# batteryless_design_revA.net
KiCad netlist of a schematic drawn in EAGLE
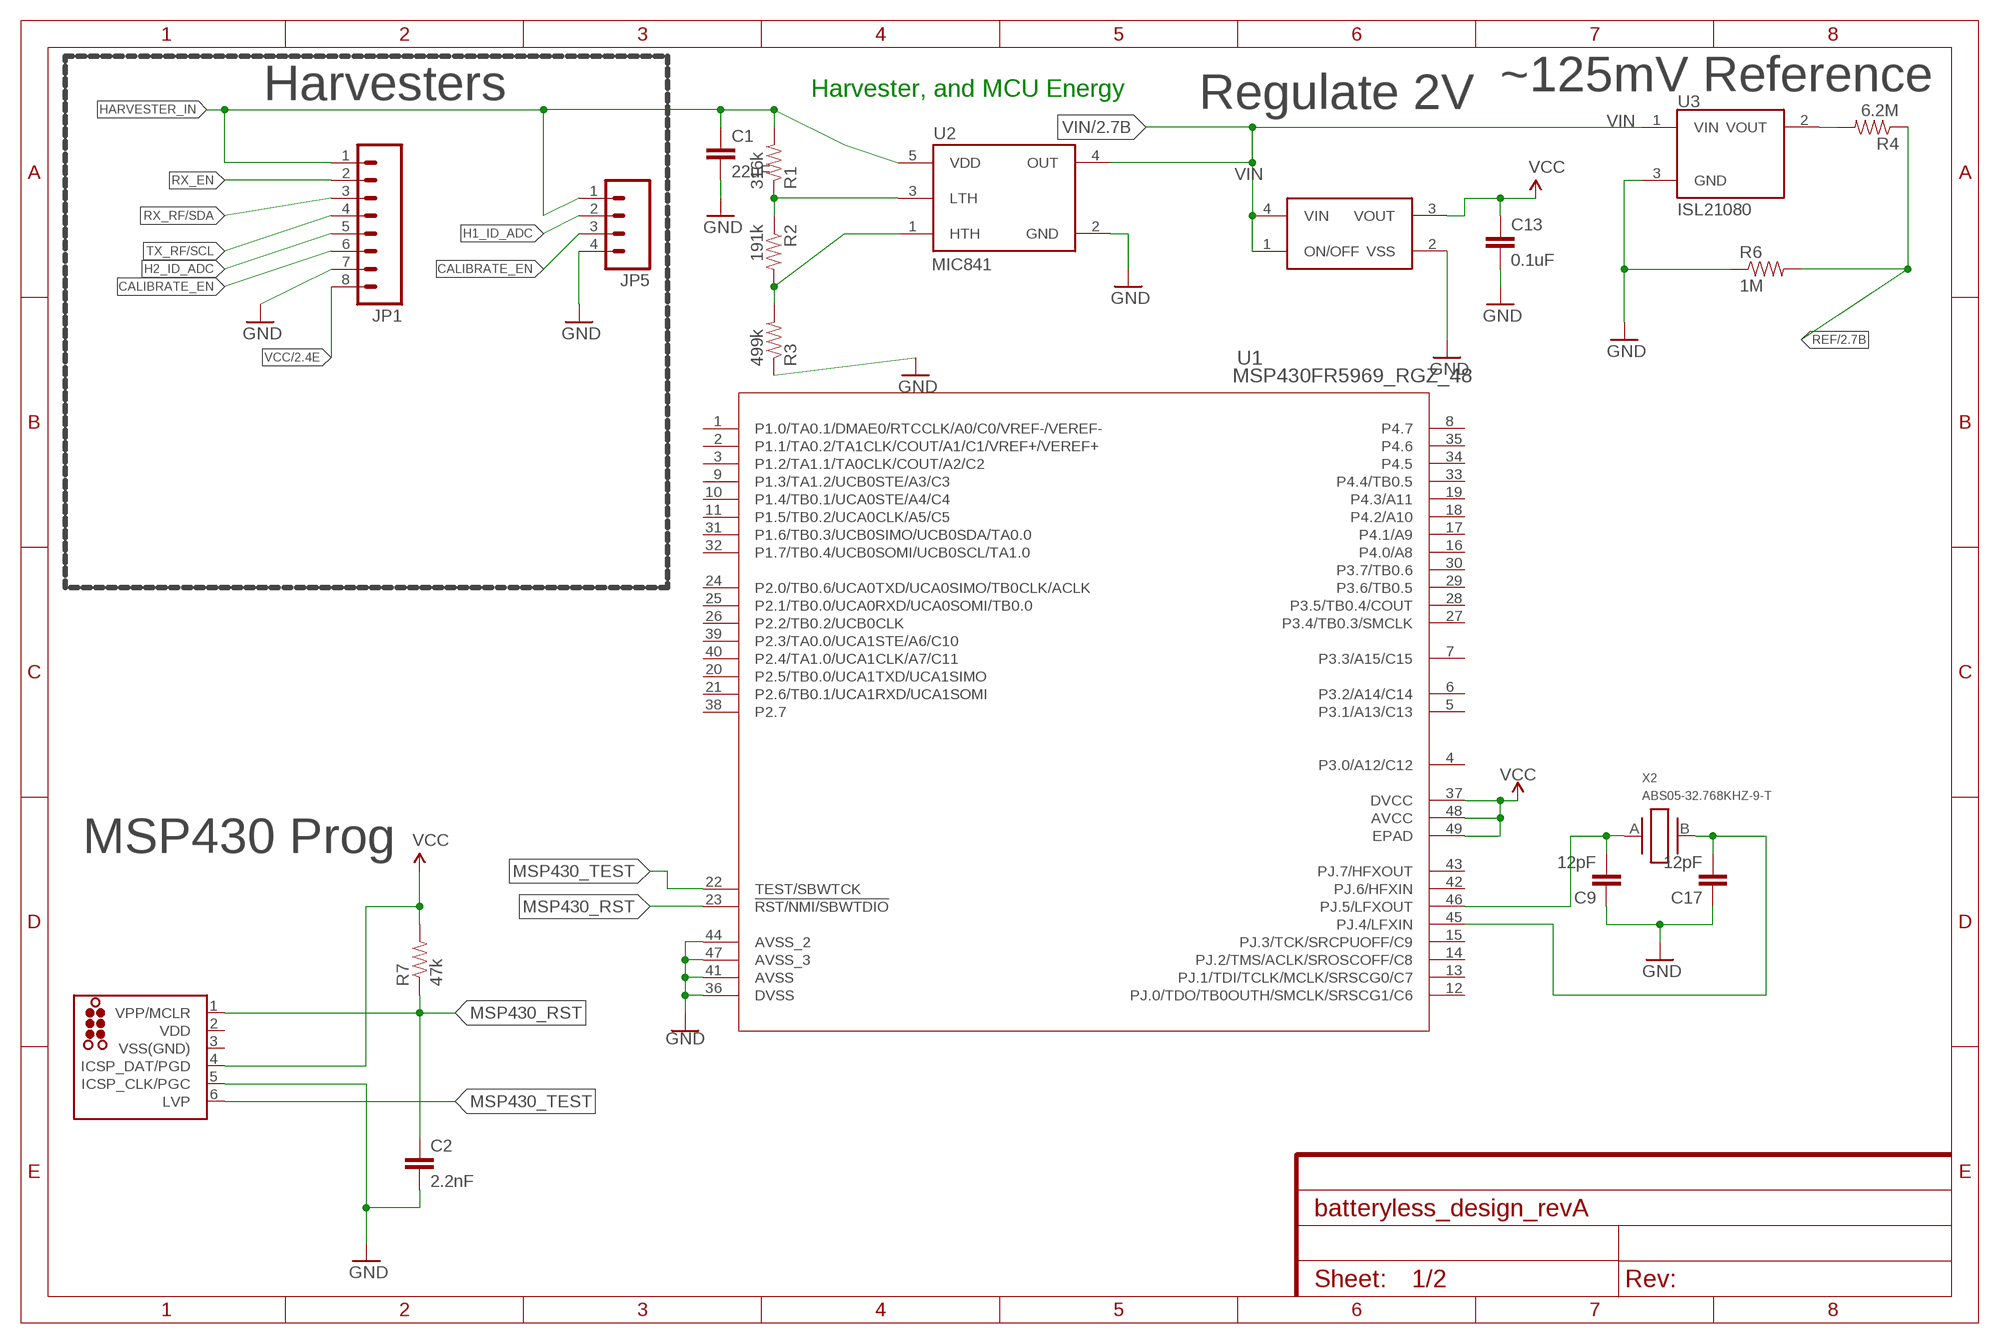
[diagram p0: schematic, sheet 1]
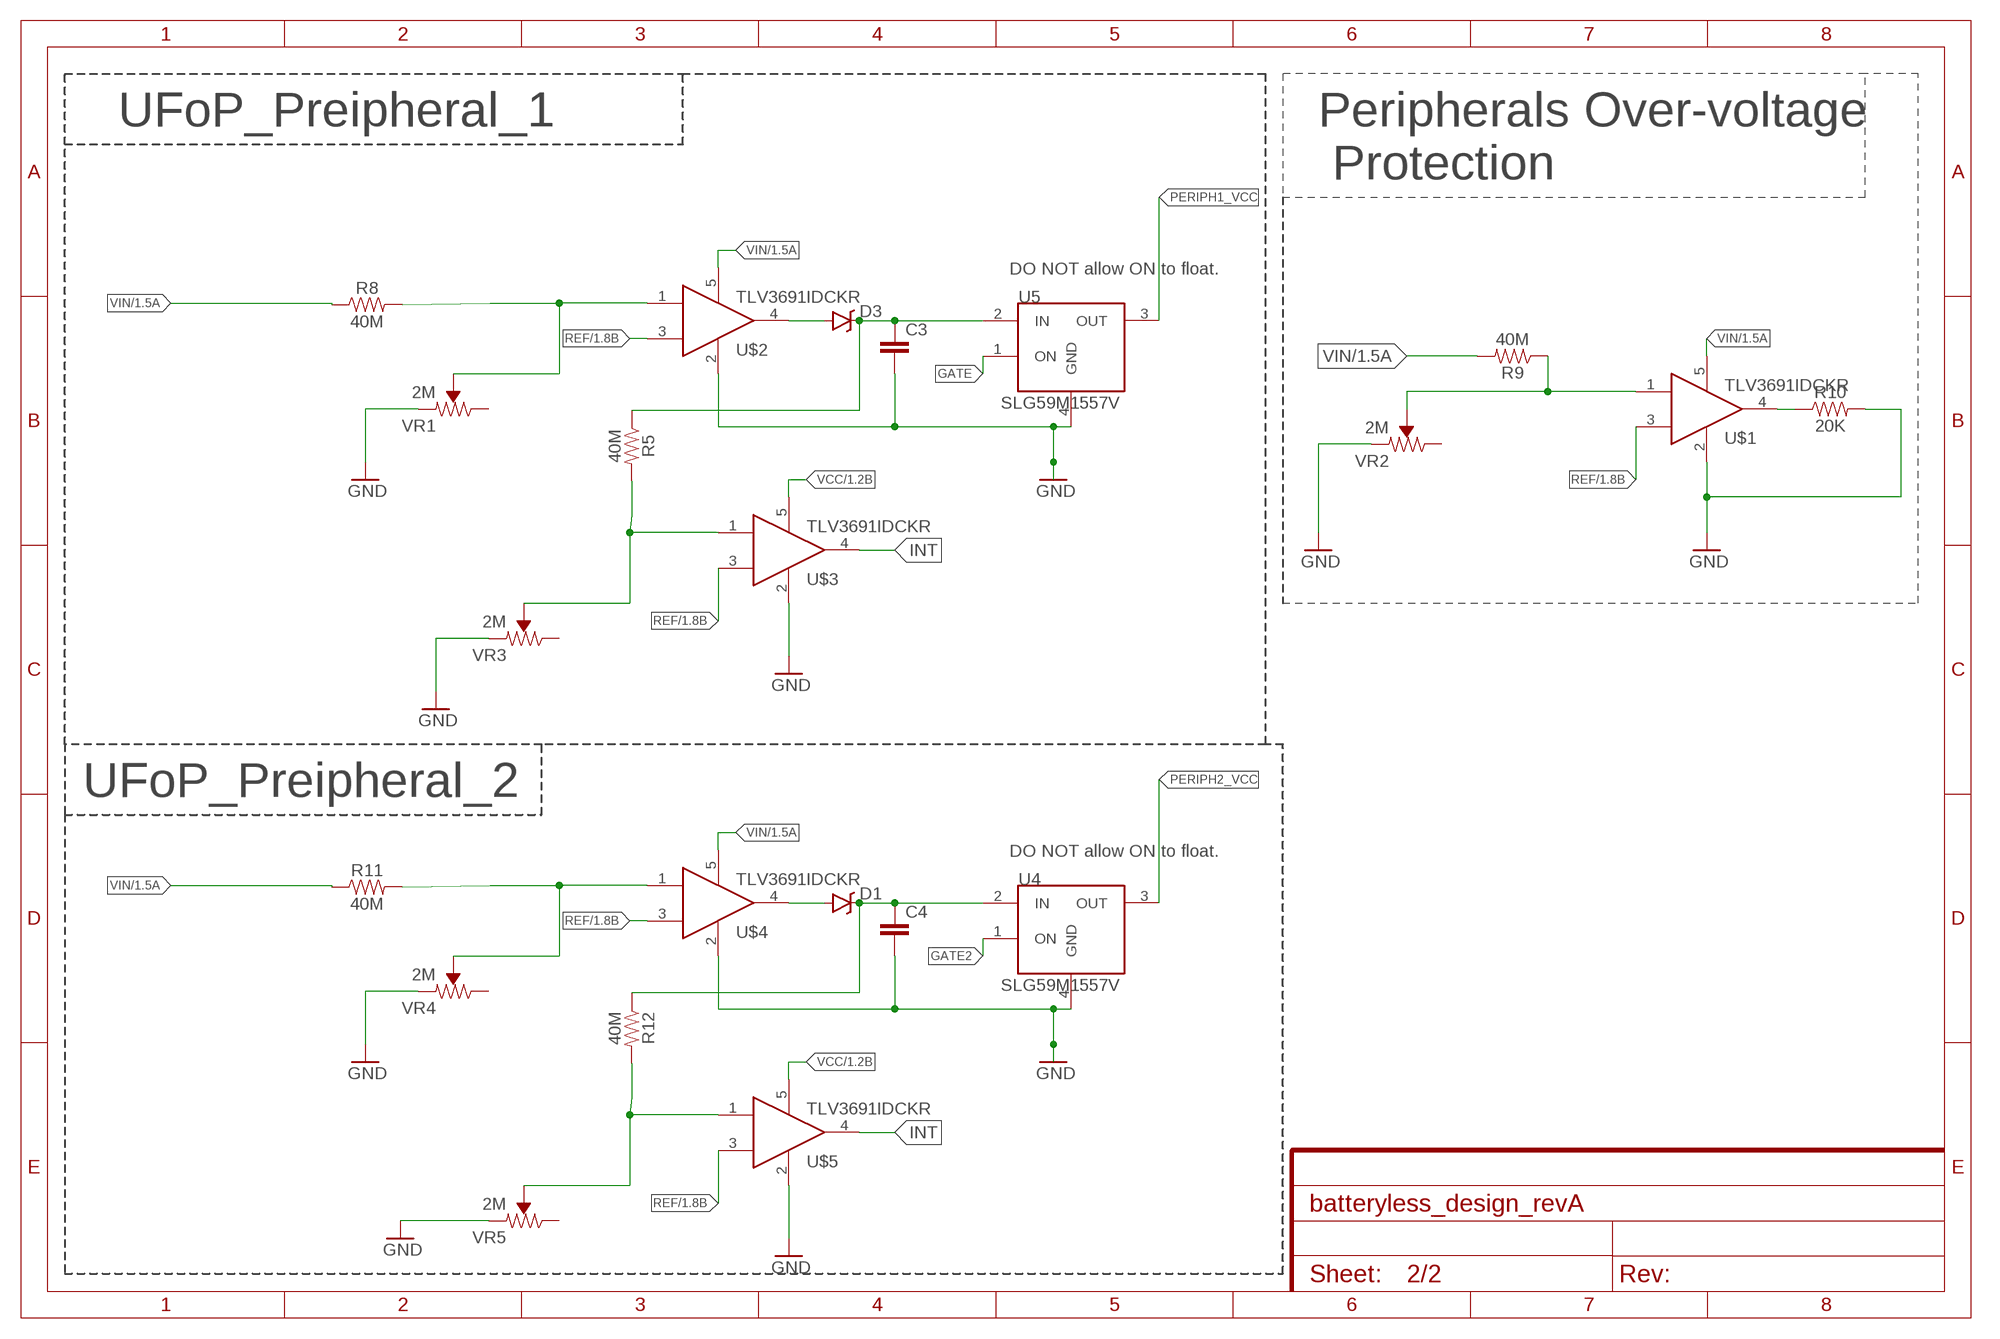
[diagram p1: schematic, sheet 2]

(export (version "E")
  (design (tool "Eeschema 10.0.6"))
  (components
    (comp (ref "C1")
      (value "22uF")
      (footprint "eagle-import:1210")
      (fields (field (name "MANUFACTURERPARTNUMBER") "  CL32A226KAJNNNE"))
      (libsource (lib "eagle-import") (part "CAP1210"))
    )
    (comp (ref "C2")
      (value "2.2nF")
      (footprint "eagle-import:0603")
      (fields (field (name "MPN") "  06035C222KAT2A"))
      (libsource (lib "eagle-import") (part "C-EU0603"))
    )
    (comp (ref "C9")
      (value "12pF")
      (footprint "eagle-import:0603")
      (fields (field (name "MPN") "CL10C120JB8NNNC"))
      (libsource (lib "eagle-import") (part "C-EU0603"))
    )
    (comp (ref "C13")
      (value "0.1uF")
      (footprint "eagle-import:0603")
      (fields (field (name "MANUFACTURERPARTNUMBER") "  0603YC104KAT2A"))
      (libsource (lib "eagle-import") (part "C-EU0603"))
    )
    (comp (ref "C17")
      (value "12pF")
      (footprint "eagle-import:0603")
      (fields (field (name "MPN") "CL10C120JB8NNNC"))
      (libsource (lib "eagle-import") (part "C-EU0603"))
    )
    (comp (ref "J1")
      (value "TC2030-MCP-NL")
      (footprint "eagle-import:TC2030-MCP-NL")
      (libsource (lib "eagle-import") (part "TC2030-MCP-NL"))
    )
    (comp (ref "JP1")
      (value "M081.27MM")
      (footprint "eagle-import:1X08-1.27MM")
      (fields (field (name "MANUFACTURERPARTNUMBER") "851-43-008-10-001000 "))
      (libsource (lib "eagle-import") (part "M081.27MM"))
    )
    (comp (ref "JP5")
      (value "M041.27MM")
      (footprint "eagle-import:1X04-1.27MM")
      (fields (field (name "MANUFACTURERPARTNUMBER") "851-43-004-10-001000 "))
      (libsource (lib "eagle-import") (part "M041.27MM"))
    )
    (comp (ref "R1")
      (value "316k")
      (footprint "eagle-import:0603")
      (fields (field (name "MANUFACTURERPARTNUMBER") "RC0603FR-07316KL "))
      (libsource (lib "eagle-import") (part "R-EU0603"))
    )
    (comp (ref "R2")
      (value "191k")
      (footprint "eagle-import:0603")
      (fields (field (name "MANUFACTURERPARTNUMBER") "RC0603FR-07191KL "))
      (libsource (lib "eagle-import") (part "R-EU0603"))
    )
    (comp (ref "R3")
      (value "499k")
      (footprint "eagle-import:0603")
      (fields (field (name "MANUFACTURERPARTNUMBER") "RC0603FR-07499KL"))
      (libsource (lib "eagle-import") (part "R-EU0603"))
    )
    (comp (ref "R4")
      (value "6.2M")
      (footprint "eagle-import:0603")
      (fields (field (name "MPN") "CRCW06036M20FKEA"))
      (libsource (lib "eagle-import") (part "R-EU0603"))
    )
    (comp (ref "R6")
      (value "1M")
      (footprint "eagle-import:0603")
      (fields (field (name "MPN") "RC0603FR-071ML"))
      (libsource (lib "eagle-import") (part "R-EU0603"))
    )
    (comp (ref "R7")
      (value "47k")
      (footprint "eagle-import:0603")
      (fields (field (name "MPN") "  CRCW060347K0JNEA"))
      (libsource (lib "eagle-import") (part "R-EU0603"))
    )
    (comp (ref "U$6")
      (value "S-1313")
      (footprint "eagle-import:SC82-AB_1PRIMARY")
      (libsource (lib "eagle-import") (part "S-1313"))
    )
    (comp (ref "U1")
      (value "MSP430FR5969_RGZ_48")
      (footprint "eagle-import:RGZ48_4P1X4P1")
      (fields (field (name "MANUFACTURER_PART_NUMBER") "msp430fr5969_rgz_48"))
      (libsource (lib "eagle-import") (part "MSP430FR5969_RGZ_48"))
    )
    (comp (ref "U2")
      (value "MIC841")
      (footprint "eagle-import:SC70-5")
      (fields (field (name "MPN") "MIC841HYC5-TR"))
      (libsource (lib "eagle-import") (part "MIC841"))
    )
    (comp (ref "U3")
      (value "ISL21080")
      (footprint "eagle-import:SOT-23")
      (fields (field (name "MPN") "ISL21080DIH309Z-TK"))
      (libsource (lib "eagle-import") (part "ISL21080"))
    )
    (comp (ref "X2")
      (value "ABS05-32.768KHZ-9-T")
      (footprint "eagle-import:ABS05")
      (fields (field (name "MPN") "ABS05-32.768KHZ-9-T "))
      (libsource (lib "eagle-import") (part "ABS05-32.768KHZ-9-T"))
    )
    (comp (ref "C3")
      (value "0.1UF-0603-25V-(+80/-20%)")
      (footprint "eagle-import:0603")
      (libsource (lib "eagle-import") (part "0.1UF-0603-25V-(+80/-20%)"))
    )
    (comp (ref "C4")
      (value "0.1UF-0603-25V-(+80/-20%)")
      (footprint "eagle-import:0603")
      (libsource (lib "eagle-import") (part "0.1UF-0603-25V-(+80/-20%)"))
    )
    (comp (ref "D1")
      (value "RB751")
      (footprint "eagle-import:SOD-523")
      (fields (field (name "MPN") "BAS40-02V-V-G-08"))
      (libsource (lib "eagle-import") (part "DIODE-SCHOTTKY-RB751"))
    )
    (comp (ref "D3")
      (value "RB751")
      (footprint "eagle-import:SOD-523")
      (fields (field (name "MPN") "BAS40-02V-V-G-08"))
      (libsource (lib "eagle-import") (part "DIODE-SCHOTTKY-RB751"))
    )
    (comp (ref "R5")
      (value "40M")
      (footprint "eagle-import:0805")
      (libsource (lib "eagle-import") (part "0.3OHM-0805-1/8W-1%"))
    )
    (comp (ref "R8")
      (value "40M")
      (footprint "eagle-import:0805")
      (libsource (lib "eagle-import") (part "0.3OHM-0805-1/8W-1%"))
    )
    (comp (ref "R9")
      (value "40M")
      (footprint "eagle-import:0805")
      (libsource (lib "eagle-import") (part "0.3OHM-0805-1/8W-1%"))
    )
    (comp (ref "R10")
      (value "20K")
      (footprint "eagle-import:0805")
      (libsource (lib "eagle-import") (part "0.3OHM-0805-1/8W-1%"))
    )
    (comp (ref "R11")
      (value "40M")
      (footprint "eagle-import:0805")
      (libsource (lib "eagle-import") (part "0.3OHM-0805-1/8W-1%"))
    )
    (comp (ref "R12")
      (value "40M")
      (footprint "eagle-import:0805")
      (libsource (lib "eagle-import") (part "0.3OHM-0805-1/8W-1%"))
    )
    (comp (ref "U$1")
      (value "TLV3691IDCKR")
      (footprint "eagle-import:SOT353")
      (libsource (lib "eagle-import") (part "TLV3691IDCKR"))
    )
    (comp (ref "U$2")
      (value "TLV3691IDCKR")
      (footprint "eagle-import:SOT353")
      (libsource (lib "eagle-import") (part "TLV3691IDCKR"))
    )
    (comp (ref "U$3")
      (value "TLV3691IDCKR")
      (footprint "eagle-import:SOT353")
      (libsource (lib "eagle-import") (part "TLV3691IDCKR"))
    )
    (comp (ref "U$4")
      (value "TLV3691IDCKR")
      (footprint "eagle-import:SOT353")
      (libsource (lib "eagle-import") (part "TLV3691IDCKR"))
    )
    (comp (ref "U$5")
      (value "TLV3691IDCKR")
      (footprint "eagle-import:SOT353")
      (libsource (lib "eagle-import") (part "TLV3691IDCKR"))
    )
    (comp (ref "U4")
      (value "SLG59M1557V")
      (footprint "eagle-import:4STDFN")
      (fields (field (name "MPN") "SLG59M1557V "))
      (libsource (lib "eagle-import") (part "SLG59M1557V"))
    )
    (comp (ref "U5")
      (value "SLG59M1557V")
      (footprint "eagle-import:4STDFN")
      (fields (field (name "MPN") "SLG59M1557V "))
      (libsource (lib "eagle-import") (part "SLG59M1557V"))
    )
    (comp (ref "VR1")
      (value "2M")
      (footprint "eagle-import:TRIMPOT-SMD-3MM-CLOSED")
      (libsource (lib "eagle-import") (part "TRIMPOT-SMD-3MM-CLOSED-1/8W-20%"))
    )
    (comp (ref "VR2")
      (value "2M")
      (footprint "eagle-import:TRIMPOT-SMD-3MM-CLOSED")
      (libsource (lib "eagle-import") (part "TRIMPOT-SMD-3MM-CLOSED-1/8W-20%"))
    )
    (comp (ref "VR3")
      (value "2M")
      (footprint "eagle-import:TRIMPOT-SMD-3MM-CLOSED")
      (libsource (lib "eagle-import") (part "TRIMPOT-SMD-3MM-CLOSED-1/8W-20%"))
    )
    (comp (ref "VR4")
      (value "2M")
      (footprint "eagle-import:TRIMPOT-SMD-3MM-CLOSED")
      (libsource (lib "eagle-import") (part "TRIMPOT-SMD-3MM-CLOSED-1/8W-20%"))
    )
    (comp (ref "VR5")
      (value "2M")
      (footprint "eagle-import:TRIMPOT-SMD-3MM-CLOSED")
      (libsource (lib "eagle-import") (part "TRIMPOT-SMD-3MM-CLOSED-1/8W-20%"))
    )
  )
  (nets
    (net (code "1") (name "CALIBRATE_EN") (class "Default")
      (node (ref "JP1") (pin "6") (pinfunction "6_6") (pintype "passive"))
      (node (ref "JP5") (pin "3") (pinfunction "3_3") (pintype "passive"))
    )
    (net (code "2") (name "GATE") (class "Default")
      (node (ref "U5") (pin "1") (pinfunction "ON_1") (pintype "bidirectional"))
    )
    (net (code "3") (name "GATE2") (class "Default")
      (node (ref "U4") (pin "1") (pinfunction "ON_1") (pintype "bidirectional"))
    )
    (net (code "4") (name "GND") (class "Default")
      (node (ref "C1") (pin "2") (pinfunction "2_2") (pintype "passive"))
      (node (ref "C13") (pin "2") (pinfunction "2_2") (pintype "passive"))
      (node (ref "C17") (pin "1") (pinfunction "1_1") (pintype "passive"))
      (node (ref "C2") (pin "2") (pinfunction "2_2") (pintype "passive"))
      (node (ref "C3") (pin "2") (pinfunction "2_2") (pintype "passive"))
      (node (ref "C4") (pin "2") (pinfunction "2_2") (pintype "passive"))
      (node (ref "C9") (pin "1") (pinfunction "1_1") (pintype "passive"))
      (node (ref "J1") (pin "5") (pinfunction "ICSP_CLK/PGC_5") (pintype "output"))
      (node (ref "JP1") (pin "7") (pinfunction "7_7") (pintype "passive"))
      (node (ref "JP5") (pin "4") (pinfunction "4_4") (pintype "passive"))
      (node (ref "R10") (pin "2") (pinfunction "2_2") (pintype "passive"))
      (node (ref "R3") (pin "1") (pinfunction "1_1") (pintype "passive"))
      (node (ref "R6") (pin "1") (pinfunction "1_1") (pintype "passive"))
      (node (ref "U$1") (pin "2") (pinfunction "2_2") (pintype "bidirectional"))
      (node (ref "U$2") (pin "2") (pinfunction "2_2") (pintype "bidirectional"))
      (node (ref "U$3") (pin "2") (pinfunction "2_2") (pintype "bidirectional"))
      (node (ref "U$4") (pin "2") (pinfunction "2_2") (pintype "bidirectional"))
      (node (ref "U$5") (pin "2") (pinfunction "2_2") (pintype "bidirectional"))
      (node (ref "U$6") (pin "2") (pinfunction "VSS_2") (pintype "bidirectional"))
      (node (ref "U1") (pin "36") (pinfunction "DVSS_36") (pintype "power_in"))
      (node (ref "U1") (pin "41") (pinfunction "AVSS_41") (pintype "power_in"))
      (node (ref "U1") (pin "44") (pinfunction "AVSS_2_44") (pintype "power_in"))
      (node (ref "U1") (pin "47") (pinfunction "AVSS_3_47") (pintype "power_in"))
      (node (ref "U2") (pin "2") (pinfunction "GND_2") (pintype "bidirectional"))
      (node (ref "U3") (pin "3") (pinfunction "GND_3") (pintype "bidirectional"))
      (node (ref "U4") (pin "4") (pinfunction "GND_4") (pintype "bidirectional"))
      (node (ref "U5") (pin "4") (pinfunction "GND_4") (pintype "bidirectional"))
      (node (ref "VR1") (pin "1") (pinfunction "CCW_1") (pintype "passive"))
      (node (ref "VR2") (pin "1") (pinfunction "CCW_1") (pintype "passive"))
      (node (ref "VR3") (pin "1") (pinfunction "CCW_1") (pintype "passive"))
      (node (ref "VR4") (pin "1") (pinfunction "CCW_1") (pintype "passive"))
      (node (ref "VR5") (pin "1") (pinfunction "CCW_1") (pintype "passive"))
    )
    (net (code "5") (name "H1_ID_ADC") (class "Default")
      (node (ref "JP5") (pin "2") (pinfunction "2_2") (pintype "passive"))
    )
    (net (code "6") (name "H2_ID_ADC") (class "Default")
      (node (ref "JP1") (pin "5") (pinfunction "5_5") (pintype "passive"))
    )
    (net (code "7") (name "HARVESTER_IN") (class "Default")
      (node (ref "C1") (pin "1") (pinfunction "1_1") (pintype "passive"))
      (node (ref "JP1") (pin "1") (pinfunction "1_1") (pintype "passive"))
      (node (ref "JP5") (pin "1") (pinfunction "1_1") (pintype "passive"))
      (node (ref "R1") (pin "2") (pinfunction "2_2") (pintype "passive"))
      (node (ref "U2") (pin "5") (pinfunction "VDD_5") (pintype "bidirectional"))
    )
    (net (code "8") (name "INT") (class "Default")
      (node (ref "U$3") (pin "4") (pinfunction "4_4") (pintype "bidirectional"))
      (node (ref "U$5") (pin "4") (pinfunction "4_4") (pintype "bidirectional"))
    )
    (net (code "9") (name "MSP430_RST") (class "Default")
      (node (ref "C2") (pin "1") (pinfunction "1_1") (pintype "passive"))
      (node (ref "J1") (pin "1") (pinfunction "VPP/MCLR_1") (pintype "passive"))
      (node (ref "R7") (pin "1") (pinfunction "1_1") (pintype "passive"))
    )
    (net (code "10") (name "MSP430_TEST") (class "Default")
      (node (ref "J1") (pin "6") (pinfunction "LVP_6") (pintype "bidirectional"))
    )
    (net (code "11") (name "Net-(D1-PadA)") (class "Default")
      (node (ref "D1") (pin "A") (pinfunction "A_A") (pintype "passive"))
      (node (ref "U$4") (pin "4") (pinfunction "4_4") (pintype "bidirectional"))
    )
    (net (code "12") (name "Net-(D3-PadA)") (class "Default")
      (node (ref "D3") (pin "A") (pinfunction "A_A") (pintype "passive"))
      (node (ref "U$2") (pin "4") (pinfunction "4_4") (pintype "bidirectional"))
    )
    (net (code "13") (name "Net-(R10-Pad1)") (class "Default")
      (node (ref "R10") (pin "1") (pinfunction "1_1") (pintype "passive"))
      (node (ref "U$1") (pin "4") (pinfunction "4_4") (pintype "bidirectional"))
    )
    (net (code "14") (name "Net-(U1-PJ.4{slash}LFXIN)") (class "Default")
      (node (ref "C17") (pin "2") (pinfunction "2_2") (pintype "passive"))
      (node (ref "U1") (pin "45") (pinfunction "PJ.4/LFXIN_45") (pintype "passive"))
      (node (ref "X2") (pin "B") (pinfunction "2_B") (pintype "bidirectional"))
    )
    (net (code "15") (name "Net-(U1-PJ.5{slash}LFXOUT)") (class "Default")
      (node (ref "C9") (pin "2") (pinfunction "2_2") (pintype "passive"))
      (node (ref "U1") (pin "46") (pinfunction "PJ.5/LFXOUT_46") (pintype "passive"))
      (node (ref "X2") (pin "A") (pinfunction "1_A") (pintype "bidirectional"))
    )
    (net (code "16") (name "Net-(U2-HTH)") (class "Default")
      (node (ref "R2") (pin "2") (pinfunction "2_2") (pintype "passive"))
      (node (ref "R3") (pin "2") (pinfunction "2_2") (pintype "passive"))
      (node (ref "U2") (pin "1") (pinfunction "HTH_1") (pintype "bidirectional"))
    )
    (net (code "17") (name "Net-(U2-LTH)") (class "Default")
      (node (ref "R1") (pin "1") (pinfunction "1_1") (pintype "passive"))
      (node (ref "R2") (pin "1") (pinfunction "1_1") (pintype "passive"))
      (node (ref "U2") (pin "3") (pinfunction "LTH_3") (pintype "bidirectional"))
    )
    (net (code "18") (name "Net-(U3-VOUT)") (class "Default")
      (node (ref "R4") (pin "2") (pinfunction "2_2") (pintype "passive"))
      (node (ref "U3") (pin "2") (pinfunction "VOUT_2") (pintype "bidirectional"))
    )
    (net (code "19") (name "Net-(U4-IN)") (class "Default")
      (node (ref "C4") (pin "1") (pinfunction "1_1") (pintype "passive"))
      (node (ref "D1") (pin "C") (pinfunction "C_C") (pintype "passive"))
      (node (ref "R12") (pin "1") (pinfunction "1_1") (pintype "passive"))
      (node (ref "U4") (pin "2") (pinfunction "IN_2") (pintype "bidirectional"))
    )
    (net (code "20") (name "Net-(U5-IN)") (class "Default")
      (node (ref "C3") (pin "1") (pinfunction "1_1") (pintype "passive"))
      (node (ref "D3") (pin "C") (pinfunction "C_C") (pintype "passive"))
      (node (ref "R5") (pin "1") (pinfunction "1_1") (pintype "passive"))
      (node (ref "U5") (pin "2") (pinfunction "IN_2") (pintype "bidirectional"))
    )
    (net (code "21") (name "Net-(VR1-WIPER)") (class "Default")
      (node (ref "R8") (pin "2") (pinfunction "2_2") (pintype "passive"))
      (node (ref "U$2") (pin "1") (pinfunction "1_1") (pintype "bidirectional"))
      (node (ref "VR1") (pin "2") (pinfunction "WIPER_2") (pintype "passive"))
    )
    (net (code "22") (name "Net-(VR2-WIPER)") (class "Default")
      (node (ref "R9") (pin "1") (pinfunction "1_1") (pintype "passive"))
      (node (ref "U$1") (pin "1") (pinfunction "1_1") (pintype "bidirectional"))
      (node (ref "VR2") (pin "2") (pinfunction "WIPER_2") (pintype "passive"))
    )
    (net (code "23") (name "Net-(VR3-WIPER)") (class "Default")
      (node (ref "R5") (pin "2") (pinfunction "2_2") (pintype "passive"))
      (node (ref "U$3") (pin "1") (pinfunction "1_1") (pintype "bidirectional"))
      (node (ref "VR3") (pin "2") (pinfunction "WIPER_2") (pintype "passive"))
    )
    (net (code "24") (name "Net-(VR4-WIPER)") (class "Default")
      (node (ref "R11") (pin "2") (pinfunction "2_2") (pintype "passive"))
      (node (ref "U$4") (pin "1") (pinfunction "1_1") (pintype "bidirectional"))
      (node (ref "VR4") (pin "2") (pinfunction "WIPER_2") (pintype "passive"))
    )
    (net (code "25") (name "Net-(VR5-WIPER)") (class "Default")
      (node (ref "R12") (pin "2") (pinfunction "2_2") (pintype "passive"))
      (node (ref "U$5") (pin "1") (pinfunction "1_1") (pintype "bidirectional"))
      (node (ref "VR5") (pin "2") (pinfunction "WIPER_2") (pintype "passive"))
    )
    (net (code "26") (name "PERIPH1_VCC") (class "Default")
      (node (ref "U5") (pin "3") (pinfunction "OUT_3") (pintype "bidirectional"))
    )
    (net (code "27") (name "PERIPH2_VCC") (class "Default")
      (node (ref "U4") (pin "3") (pinfunction "OUT_3") (pintype "bidirectional"))
    )
    (net (code "28") (name "REF") (class "Default")
      (node (ref "R4") (pin "1") (pinfunction "1_1") (pintype "passive"))
      (node (ref "R6") (pin "2") (pinfunction "2_2") (pintype "passive"))
      (node (ref "U$1") (pin "3") (pinfunction "3_3") (pintype "bidirectional"))
      (node (ref "U$2") (pin "3") (pinfunction "3_3") (pintype "bidirectional"))
      (node (ref "U$3") (pin "3") (pinfunction "3_3") (pintype "bidirectional"))
      (node (ref "U$4") (pin "3") (pinfunction "3_3") (pintype "bidirectional"))
      (node (ref "U$5") (pin "3") (pinfunction "3_3") (pintype "bidirectional"))
    )
    (net (code "29") (name "RX_EN") (class "Default")
      (node (ref "JP1") (pin "2") (pinfunction "2_2") (pintype "passive"))
    )
    (net (code "30") (name "RX_RF{slash}SDA") (class "Default")
      (node (ref "JP1") (pin "3") (pinfunction "3_3") (pintype "passive"))
    )
    (net (code "31") (name "TX_RF{slash}SCL") (class "Default")
      (node (ref "JP1") (pin "4") (pinfunction "4_4") (pintype "passive"))
    )
    (net (code "32") (name "VCC") (class "Default")
      (node (ref "C13") (pin "1") (pinfunction "1_1") (pintype "passive"))
      (node (ref "J1") (pin "4") (pinfunction "ICSP_DAT/PGD_4") (pintype "bidirectional"))
      (node (ref "JP1") (pin "8") (pinfunction "8_8") (pintype "passive"))
      (node (ref "R7") (pin "2") (pinfunction "2_2") (pintype "passive"))
      (node (ref "U$3") (pin "5") (pinfunction "5_5") (pintype "bidirectional"))
      (node (ref "U$5") (pin "5") (pinfunction "5_5") (pintype "bidirectional"))
      (node (ref "U$6") (pin "3") (pinfunction "VOUT_3") (pintype "bidirectional"))
      (node (ref "U1") (pin "37") (pinfunction "DVCC_37") (pintype "power_in"))
      (node (ref "U1") (pin "48") (pinfunction "AVCC_48") (pintype "power_in"))
      (node (ref "U1") (pin "49") (pinfunction "EPAD_49") (pintype "passive"))
    )
    (net (code "33") (name "VDD") (class "Default")
      (node (ref "J1") (pin "2") (pinfunction "VDD_2") (pintype "power_in"))
    )
    (net (code "34") (name "VIN") (class "Default")
      (node (ref "R11") (pin "1") (pinfunction "1_1") (pintype "passive"))
      (node (ref "R8") (pin "1") (pinfunction "1_1") (pintype "passive"))
      (node (ref "R9") (pin "2") (pinfunction "2_2") (pintype "passive"))
      (node (ref "U$1") (pin "5") (pinfunction "5_5") (pintype "bidirectional"))
      (node (ref "U$2") (pin "5") (pinfunction "5_5") (pintype "bidirectional"))
      (node (ref "U$4") (pin "5") (pinfunction "5_5") (pintype "bidirectional"))
      (node (ref "U$6") (pin "1") (pinfunction "ON/OFF_1") (pintype "bidirectional"))
      (node (ref "U$6") (pin "4") (pinfunction "VIN_4") (pintype "bidirectional"))
      (node (ref "U2") (pin "4") (pinfunction "OUT_4") (pintype "bidirectional"))
      (node (ref "U3") (pin "1") (pinfunction "VIN_1") (pintype "bidirectional"))
    )
    (net (code "35") (name "VSS(GND)") (class "Default")
      (node (ref "J1") (pin "3") (pinfunction "VSS(GND)_3") (pintype "power_in"))
    )
    (net (code "36") (name "unconnected-(U1-P1.0{slash}TA0.1{slash}DMAE0{slash}RTCCLK{slash}A0{slash}C0{slash}VREF-{slash}VEREF--Pad1)") (class "Default")
      (node (ref "U1") (pin "1") (pinfunction "P1.0/TA0.1/DMAE0/RTCCLK/A0/C0/VREF-/VEREF-_1") (pintype "passive"))
    )
    (net (code "37") (name "unconnected-(U1-P1.1{slash}TA0.2{slash}TA1CLK{slash}COUT{slash}A1{slash}C1{slash}VREF+{slash}VEREF+-Pad2)") (class "Default")
      (node (ref "U1") (pin "2") (pinfunction "P1.1/TA0.2/TA1CLK/COUT/A1/C1/VREF+/VEREF+_2") (pintype "passive"))
    )
    (net (code "38") (name "unconnected-(U1-P1.2{slash}TA1.1{slash}TA0CLK{slash}COUT{slash}A2{slash}C2-Pad3)") (class "Default")
      (node (ref "U1") (pin "3") (pinfunction "P1.2/TA1.1/TA0CLK/COUT/A2/C2_3") (pintype "passive"))
    )
    (net (code "39") (name "unconnected-(U1-P1.3{slash}TA1.2{slash}UCB0STE{slash}A3{slash}C3-Pad9)") (class "Default")
      (node (ref "U1") (pin "9") (pinfunction "P1.3/TA1.2/UCB0STE/A3/C3_9") (pintype "passive"))
    )
    (net (code "40") (name "unconnected-(U1-P1.4{slash}TB0.1{slash}UCA0STE{slash}A4{slash}C4-Pad10)") (class "Default")
      (node (ref "U1") (pin "10") (pinfunction "P1.4/TB0.1/UCA0STE/A4/C4_10") (pintype "passive"))
    )
    (net (code "41") (name "unconnected-(U1-P1.5{slash}TB0.2{slash}UCA0CLK{slash}A5{slash}C5-Pad11)") (class "Default")
      (node (ref "U1") (pin "11") (pinfunction "P1.5/TB0.2/UCA0CLK/A5/C5_11") (pintype "passive"))
    )
    (net (code "42") (name "unconnected-(U1-P1.6{slash}TB0.3{slash}UCB0SIMO{slash}UCB0SDA{slash}TA0.0-Pad31)") (class "Default")
      (node (ref "U1") (pin "31") (pinfunction "P1.6/TB0.3/UCB0SIMO/UCB0SDA/TA0.0_31") (pintype "passive"))
    )
    (net (code "43") (name "unconnected-(U1-P1.7{slash}TB0.4{slash}UCB0SOMI{slash}UCB0SCL{slash}TA1.0-Pad32)") (class "Default")
      (node (ref "U1") (pin "32") (pinfunction "P1.7/TB0.4/UCB0SOMI/UCB0SCL/TA1.0_32") (pintype "passive"))
    )
    (net (code "44") (name "unconnected-(U1-P2.0{slash}TB0.6{slash}UCA0TXD{slash}UCA0SIMO{slash}TB0CLK{slash}ACLK-Pad24)") (class "Default")
      (node (ref "U1") (pin "24") (pinfunction "P2.0/TB0.6/UCA0TXD/UCA0SIMO/TB0CLK/ACLK_24") (pintype "passive"))
    )
    (net (code "45") (name "unconnected-(U1-P2.1{slash}TB0.0{slash}UCA0RXD{slash}UCA0SOMI{slash}TB0.0-Pad25)") (class "Default")
      (node (ref "U1") (pin "25") (pinfunction "P2.1/TB0.0/UCA0RXD/UCA0SOMI/TB0.0_25") (pintype "passive"))
    )
    (net (code "46") (name "unconnected-(U1-P2.2{slash}TB0.2{slash}UCB0CLK-Pad26)") (class "Default")
      (node (ref "U1") (pin "26") (pinfunction "P2.2/TB0.2/UCB0CLK_26") (pintype "passive"))
    )
    (net (code "47") (name "unconnected-(U1-P2.3{slash}TA0.0{slash}UCA1STE{slash}A6{slash}C10-Pad39)") (class "Default")
      (node (ref "U1") (pin "39") (pinfunction "P2.3/TA0.0/UCA1STE/A6/C10_39") (pintype "passive"))
    )
    (net (code "48") (name "unconnected-(U1-P2.4{slash}TA1.0{slash}UCA1CLK{slash}A7{slash}C11-Pad40)") (class "Default")
      (node (ref "U1") (pin "40") (pinfunction "P2.4/TA1.0/UCA1CLK/A7/C11_40") (pintype "passive"))
    )
    (net (code "49") (name "unconnected-(U1-P2.5{slash}TB0.0{slash}UCA1TXD{slash}UCA1SIMO-Pad20)") (class "Default")
      (node (ref "U1") (pin "20") (pinfunction "P2.5/TB0.0/UCA1TXD/UCA1SIMO_20") (pintype "passive"))
    )
    (net (code "50") (name "unconnected-(U1-P2.6{slash}TB0.1{slash}UCA1RXD{slash}UCA1SOMI-Pad21)") (class "Default")
      (node (ref "U1") (pin "21") (pinfunction "P2.6/TB0.1/UCA1RXD/UCA1SOMI_21") (pintype "passive"))
    )
    (net (code "51") (name "unconnected-(U1-P2.7-Pad38)") (class "Default")
      (node (ref "U1") (pin "38") (pinfunction "P2.7_38") (pintype "passive"))
    )
    (net (code "52") (name "unconnected-(U1-P3.0{slash}A12{slash}C12-Pad4)") (class "Default")
      (node (ref "U1") (pin "4") (pinfunction "P3.0/A12/C12_4") (pintype "passive"))
    )
    (net (code "53") (name "unconnected-(U1-P3.1{slash}A13{slash}C13-Pad5)") (class "Default")
      (node (ref "U1") (pin "5") (pinfunction "P3.1/A13/C13_5") (pintype "passive"))
    )
    (net (code "54") (name "unconnected-(U1-P3.2{slash}A14{slash}C14-Pad6)") (class "Default")
      (node (ref "U1") (pin "6") (pinfunction "P3.2/A14/C14_6") (pintype "passive"))
    )
    (net (code "55") (name "unconnected-(U1-P3.3{slash}A15{slash}C15-Pad7)") (class "Default")
      (node (ref "U1") (pin "7") (pinfunction "P3.3/A15/C15_7") (pintype "passive"))
    )
    (net (code "56") (name "unconnected-(U1-P3.4{slash}TB0.3{slash}SMCLK-Pad27)") (class "Default")
      (node (ref "U1") (pin "27") (pinfunction "P3.4/TB0.3/SMCLK_27") (pintype "passive"))
    )
    (net (code "57") (name "unconnected-(U1-P3.5{slash}TB0.4{slash}COUT-Pad28)") (class "Default")
      (node (ref "U1") (pin "28") (pinfunction "P3.5/TB0.4/COUT_28") (pintype "passive"))
    )
    (net (code "58") (name "unconnected-(U1-P3.6{slash}TB0.5-Pad29)") (class "Default")
      (node (ref "U1") (pin "29") (pinfunction "P3.6/TB0.5_29") (pintype "passive"))
    )
    (net (code "59") (name "unconnected-(U1-P3.7{slash}TB0.6-Pad30)") (class "Default")
      (node (ref "U1") (pin "30") (pinfunction "P3.7/TB0.6_30") (pintype "passive"))
    )
    (net (code "60") (name "unconnected-(U1-P4.0{slash}A8-Pad16)") (class "Default")
      (node (ref "U1") (pin "16") (pinfunction "P4.0/A8_16") (pintype "passive"))
    )
    (net (code "61") (name "unconnected-(U1-P4.1{slash}A9-Pad17)") (class "Default")
      (node (ref "U1") (pin "17") (pinfunction "P4.1/A9_17") (pintype "passive"))
    )
    (net (code "62") (name "unconnected-(U1-P4.2{slash}A10-Pad18)") (class "Default")
      (node (ref "U1") (pin "18") (pinfunction "P4.2/A10_18") (pintype "passive"))
    )
    (net (code "63") (name "unconnected-(U1-P4.3{slash}A11-Pad19)") (class "Default")
      (node (ref "U1") (pin "19") (pinfunction "P4.3/A11_19") (pintype "passive"))
    )
    (net (code "64") (name "unconnected-(U1-P4.4{slash}TB0.5-Pad33)") (class "Default")
      (node (ref "U1") (pin "33") (pinfunction "P4.4/TB0.5_33") (pintype "passive"))
    )
    (net (code "65") (name "unconnected-(U1-P4.5-Pad34)") (class "Default")
      (node (ref "U1") (pin "34") (pinfunction "P4.5_34") (pintype "passive"))
    )
    (net (code "66") (name "unconnected-(U1-P4.6-Pad35)") (class "Default")
      (node (ref "U1") (pin "35") (pinfunction "P4.6_35") (pintype "passive"))
    )
    (net (code "67") (name "unconnected-(U1-P4.7-Pad8)") (class "Default")
      (node (ref "U1") (pin "8") (pinfunction "P4.7_8") (pintype "passive"))
    )
    (net (code "68") (name "unconnected-(U1-PJ.0{slash}TDO{slash}TB0OUTH{slash}SMCLK{slash}SRSCG1{slash}C6-Pad12)") (class "Default")
      (node (ref "U1") (pin "12") (pinfunction "PJ.0/TDO/TB0OUTH/SMCLK/SRSCG1/C6_12") (pintype "passive"))
    )
    (net (code "69") (name "unconnected-(U1-PJ.1{slash}TDI{slash}TCLK{slash}MCLK{slash}SRSCG0{slash}C7-Pad13)") (class "Default")
      (node (ref "U1") (pin "13") (pinfunction "PJ.1/TDI/TCLK/MCLK/SRSCG0/C7_13") (pintype "passive"))
    )
    (net (code "70") (name "unconnected-(U1-PJ.2{slash}TMS{slash}ACLK{slash}SROSCOFF{slash}C8-Pad14)") (class "Default")
      (node (ref "U1") (pin "14") (pinfunction "PJ.2/TMS/ACLK/SROSCOFF/C8_14") (pintype "passive"))
    )
    (net (code "71") (name "unconnected-(U1-PJ.3{slash}TCK{slash}SRCPUOFF{slash}C9-Pad15)") (class "Default")
      (node (ref "U1") (pin "15") (pinfunction "PJ.3/TCK/SRCPUOFF/C9_15") (pintype "passive"))
    )
    (net (code "72") (name "unconnected-(U1-PJ.6{slash}HFXIN-Pad42)") (class "Default")
      (node (ref "U1") (pin "42") (pinfunction "PJ.6/HFXIN_42") (pintype "passive"))
    )
    (net (code "73") (name "unconnected-(U1-PJ.7{slash}HFXOUT-Pad43)") (class "Default")
      (node (ref "U1") (pin "43") (pinfunction "PJ.7/HFXOUT_43") (pintype "passive"))
    )
    (net (code "74") (name "unconnected-(U1-TEST{slash}SBWTCK-Pad22)") (class "Default")
      (node (ref "U1") (pin "22") (pinfunction "TEST/SBWTCK_22") (pintype "input"))
    )
    (net (code "75") (name "unconnected-(U1-~{RST{slash}NMI{slash}SBWTDIO}-Pad23)") (class "Default")
      (node (ref "U1") (pin "23") (pinfunction "~{RST/NMI/SBWTDIO}_23") (pintype "passive"))
    )
    (net (code "76") (name "unconnected-(VR1-CW-Pad3)") (class "Default")
      (node (ref "VR1") (pin "3") (pinfunction "CW_3") (pintype "passive"))
    )
    (net (code "77") (name "unconnected-(VR2-CW-Pad3)") (class "Default")
      (node (ref "VR2") (pin "3") (pinfunction "CW_3") (pintype "passive"))
    )
    (net (code "78") (name "unconnected-(VR3-CW-Pad3)") (class "Default")
      (node (ref "VR3") (pin "3") (pinfunction "CW_3") (pintype "passive"))
    )
    (net (code "79") (name "unconnected-(VR4-CW-Pad3)") (class "Default")
      (node (ref "VR4") (pin "3") (pinfunction "CW_3") (pintype "passive"))
    )
    (net (code "80") (name "unconnected-(VR5-CW-Pad3)") (class "Default")
      (node (ref "VR5") (pin "3") (pinfunction "CW_3") (pintype "passive"))
    )
  )
)
